# Humidity_TI.net
KiCad netlist of a schematic drawn in EAGLE
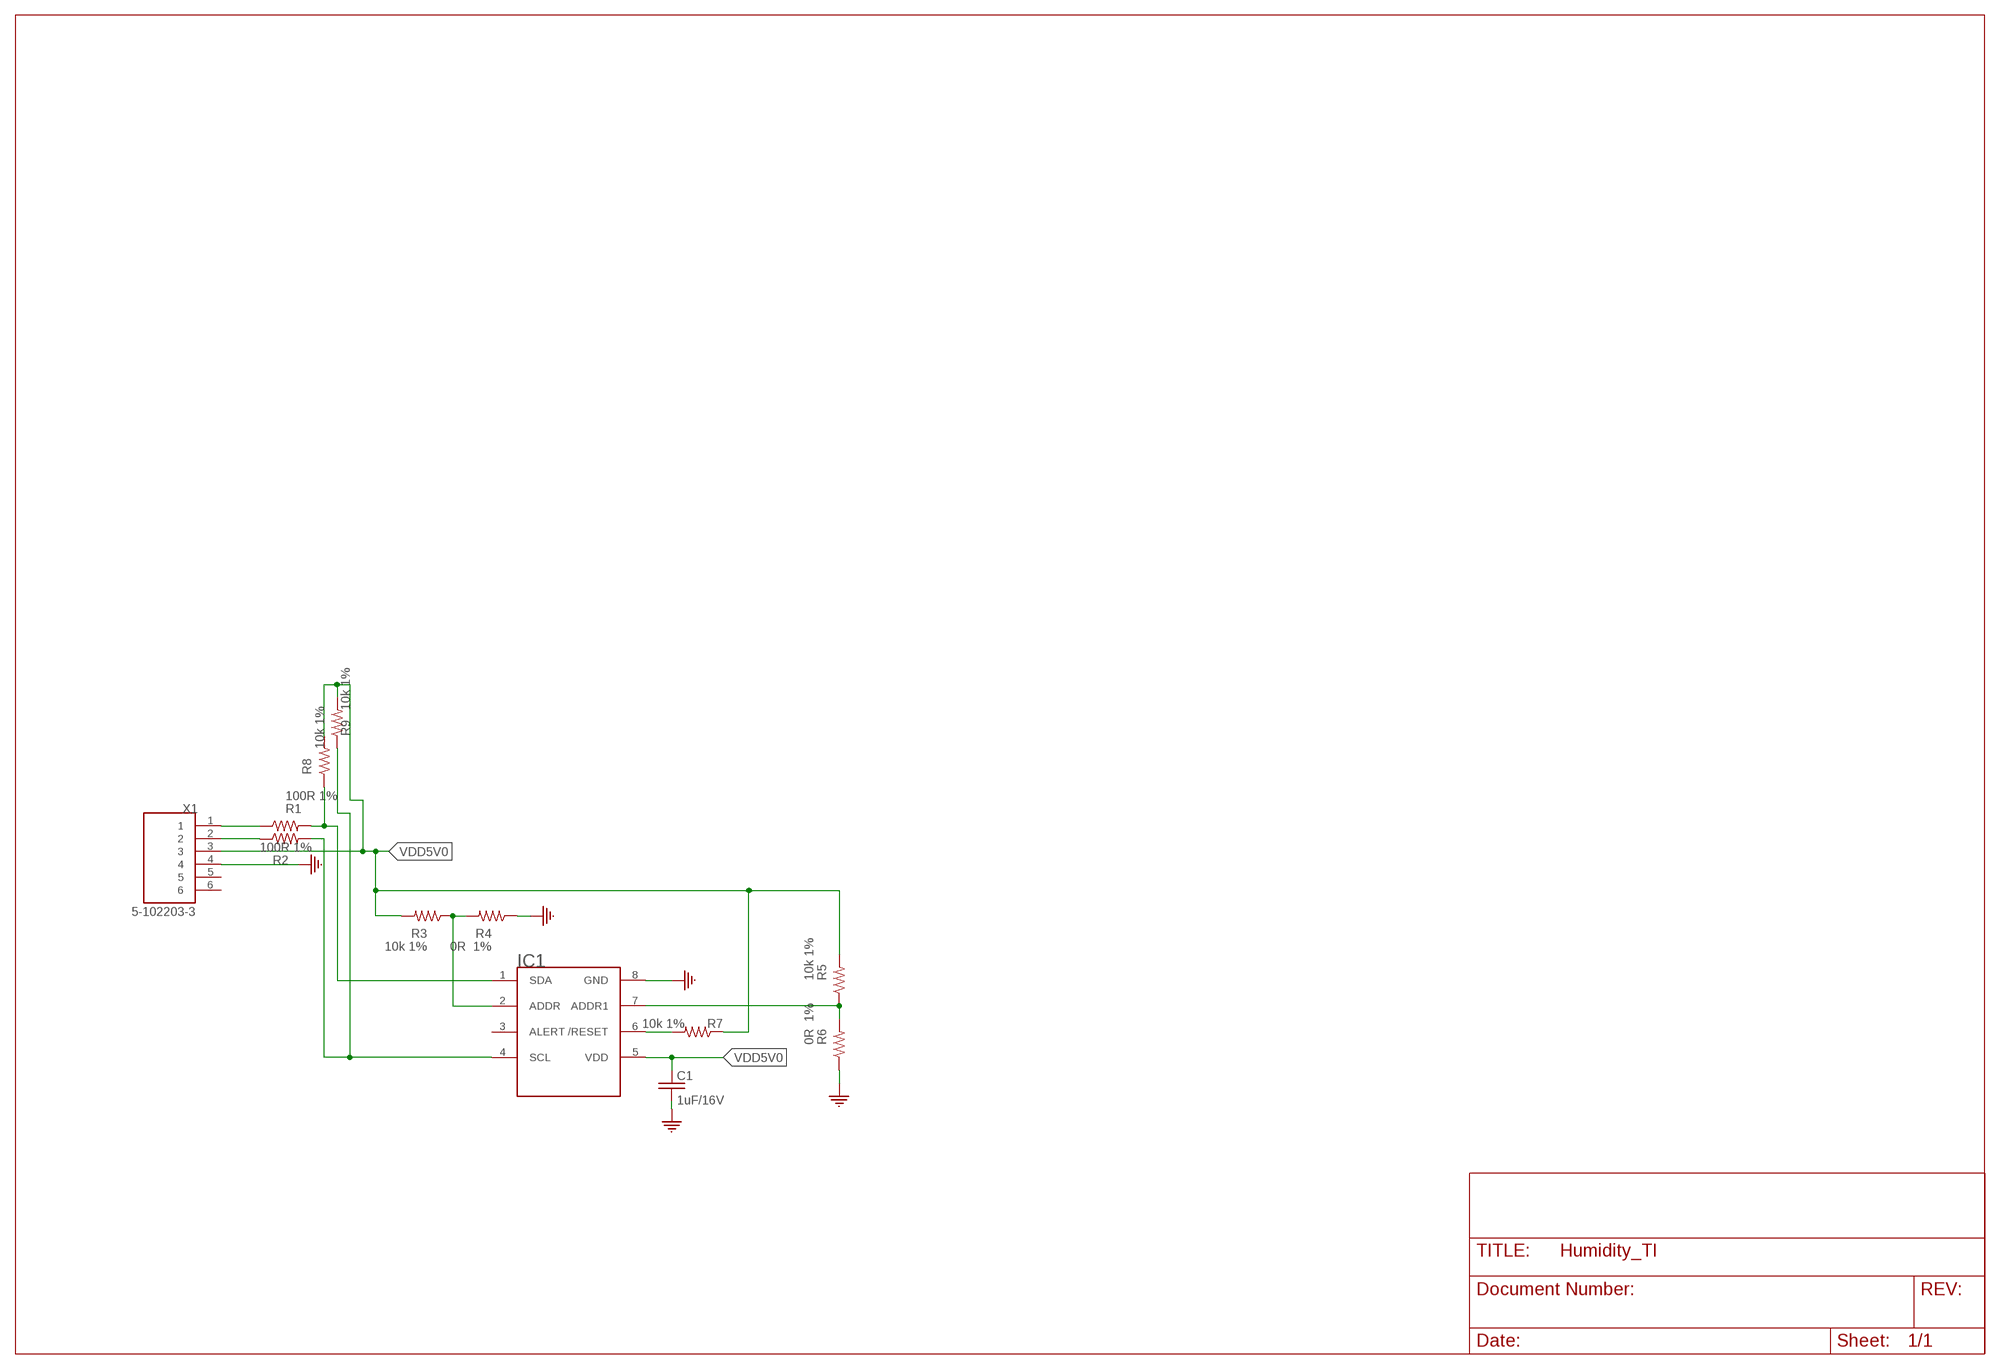
[diagram p0: schematic, sheet 1]

(export (version "E")
  (design (tool "Eeschema 10.0.6"))
  (components
    (comp (ref "C1")
      (value "1uF/16V")
      (footprint "eagle-import:EIA0603")
      (libsource (lib "eagle-import") (part "C_0603EIA0603"))
    )
    (comp (ref "IC1")
      (value "HDC3021-Q1")
      (footprint "eagle-import:WSON8")
      (fields (field (name "MFR") "Texas Instruments"))
      (libsource (lib "eagle-import") (part "HDC3021-Q1"))
    )
    (comp (ref "R1")
      (value "100R 1%")
      (footprint "eagle-import:EIA0603")
      (libsource (lib "eagle-import") (part "R_0603"))
    )
    (comp (ref "R2")
      (value "100R 1%")
      (footprint "eagle-import:EIA0603")
      (libsource (lib "eagle-import") (part "R_0603"))
    )
    (comp (ref "R3")
      (value "10k 1%")
      (footprint "eagle-import:EIA0603")
      (libsource (lib "eagle-import") (part "R_0603"))
    )
    (comp (ref "R4")
      (value "0R 1%")
      (footprint "eagle-import:EIA0603")
      (libsource (lib "eagle-import") (part "R_0603"))
    )
    (comp (ref "R5")
      (value "10k 1%")
      (footprint "eagle-import:EIA0603")
      (libsource (lib "eagle-import") (part "R_0603"))
    )
    (comp (ref "R6")
      (value "0R 1%")
      (footprint "eagle-import:EIA0603")
      (libsource (lib "eagle-import") (part "R_0603"))
    )
    (comp (ref "R7")
      (value "10k 1%")
      (footprint "eagle-import:EIA0603")
      (libsource (lib "eagle-import") (part "R_0603"))
    )
    (comp (ref "R8")
      (value "10k 1%")
      (footprint "eagle-import:EIA0603")
      (libsource (lib "eagle-import") (part "R_0603"))
    )
    (comp (ref "R9")
      (value "10k 1%")
      (footprint "eagle-import:EIA0603")
      (libsource (lib "eagle-import") (part "R_0603"))
    )
    (comp (ref "X1")
      (value "5-102203-3")
      (footprint "eagle-import:TE_5-102203-3")
      (fields (field (name "MFR") "TE Connectivity"))
      (libsource (lib "eagle-import") (part "5-102203-3"))
    )
  )
  (nets
    (net (code "1") (name "GND") (class "Default")
      (node (ref "C1") (pin "2") (pinfunction "2_2") (pintype "passive"))
      (node (ref "IC1") (pin "8") (pinfunction "GND_8") (pintype "bidirectional"))
      (node (ref "R4") (pin "1") (pinfunction "1_1") (pintype "passive"))
      (node (ref "R6") (pin "1") (pinfunction "1_1") (pintype "passive"))
      (node (ref "X1") (pin "4") (pinfunction "4_4") (pintype "passive"))
    )
    (net (code "2") (name "Net-(IC1-ADDR)") (class "Default")
      (node (ref "IC1") (pin "2") (pinfunction "ADDR_2") (pintype "bidirectional"))
      (node (ref "R3") (pin "1") (pinfunction "1_1") (pintype "passive"))
      (node (ref "R4") (pin "2") (pinfunction "2_2") (pintype "passive"))
    )
    (net (code "3") (name "Net-(IC1-ADDR1)") (class "Default")
      (node (ref "IC1") (pin "7") (pinfunction "ADDR1_7") (pintype "bidirectional"))
      (node (ref "R5") (pin "1") (pinfunction "1_1") (pintype "passive"))
      (node (ref "R6") (pin "2") (pinfunction "2_2") (pintype "passive"))
    )
    (net (code "4") (name "Net-(IC1-SCL)") (class "Default")
      (node (ref "IC1") (pin "4") (pinfunction "SCL_4") (pintype "bidirectional"))
      (node (ref "R2") (pin "2") (pinfunction "2_2") (pintype "passive"))
      (node (ref "R9") (pin "1") (pinfunction "1_1") (pintype "passive"))
    )
    (net (code "5") (name "Net-(IC1-SDA)") (class "Default")
      (node (ref "IC1") (pin "1") (pinfunction "SDA_1") (pintype "bidirectional"))
      (node (ref "R1") (pin "2") (pinfunction "2_2") (pintype "passive"))
      (node (ref "R8") (pin "1") (pinfunction "1_1") (pintype "passive"))
    )
    (net (code "6") (name "Net-(IC1-{slash}RESET)") (class "Default")
      (node (ref "IC1") (pin "6") (pinfunction "/RESET_6") (pintype "bidirectional"))
      (node (ref "R7") (pin "2") (pinfunction "2_2") (pintype "passive"))
    )
    (net (code "7") (name "Net-(R1-Pad1)") (class "Default")
      (node (ref "R1") (pin "1") (pinfunction "1_1") (pintype "passive"))
      (node (ref "X1") (pin "1") (pinfunction "1_1") (pintype "passive"))
    )
    (net (code "8") (name "Net-(R2-Pad1)") (class "Default")
      (node (ref "R2") (pin "1") (pinfunction "1_1") (pintype "passive"))
      (node (ref "X1") (pin "2") (pinfunction "2_2") (pintype "passive"))
    )
    (net (code "9") (name "VDD5V0") (class "Default")
      (node (ref "C1") (pin "1") (pinfunction "1_1") (pintype "passive"))
      (node (ref "IC1") (pin "5") (pinfunction "VDD_5") (pintype "bidirectional"))
      (node (ref "R3") (pin "2") (pinfunction "2_2") (pintype "passive"))
      (node (ref "R5") (pin "2") (pinfunction "2_2") (pintype "passive"))
      (node (ref "R7") (pin "1") (pinfunction "1_1") (pintype "passive"))
      (node (ref "R8") (pin "2") (pinfunction "2_2") (pintype "passive"))
      (node (ref "R9") (pin "2") (pinfunction "2_2") (pintype "passive"))
      (node (ref "X1") (pin "3") (pinfunction "3_3") (pintype "passive"))
    )
    (net (code "10") (name "unconnected-(IC1-ALERT-Pad3)") (class "Default")
      (node (ref "IC1") (pin "3") (pinfunction "ALERT_3") (pintype "bidirectional"))
    )
    (net (code "11") (name "unconnected-(X1-Pad5)") (class "Default")
      (node (ref "X1") (pin "5") (pinfunction "5_5") (pintype "passive"))
    )
    (net (code "12") (name "unconnected-(X1-Pad6)") (class "Default")
      (node (ref "X1") (pin "6") (pinfunction "6_6") (pintype "passive"))
    )
  )
)
